# Aux_Connectors.net
KiCad netlist of a schematic drawn in Altium Designer
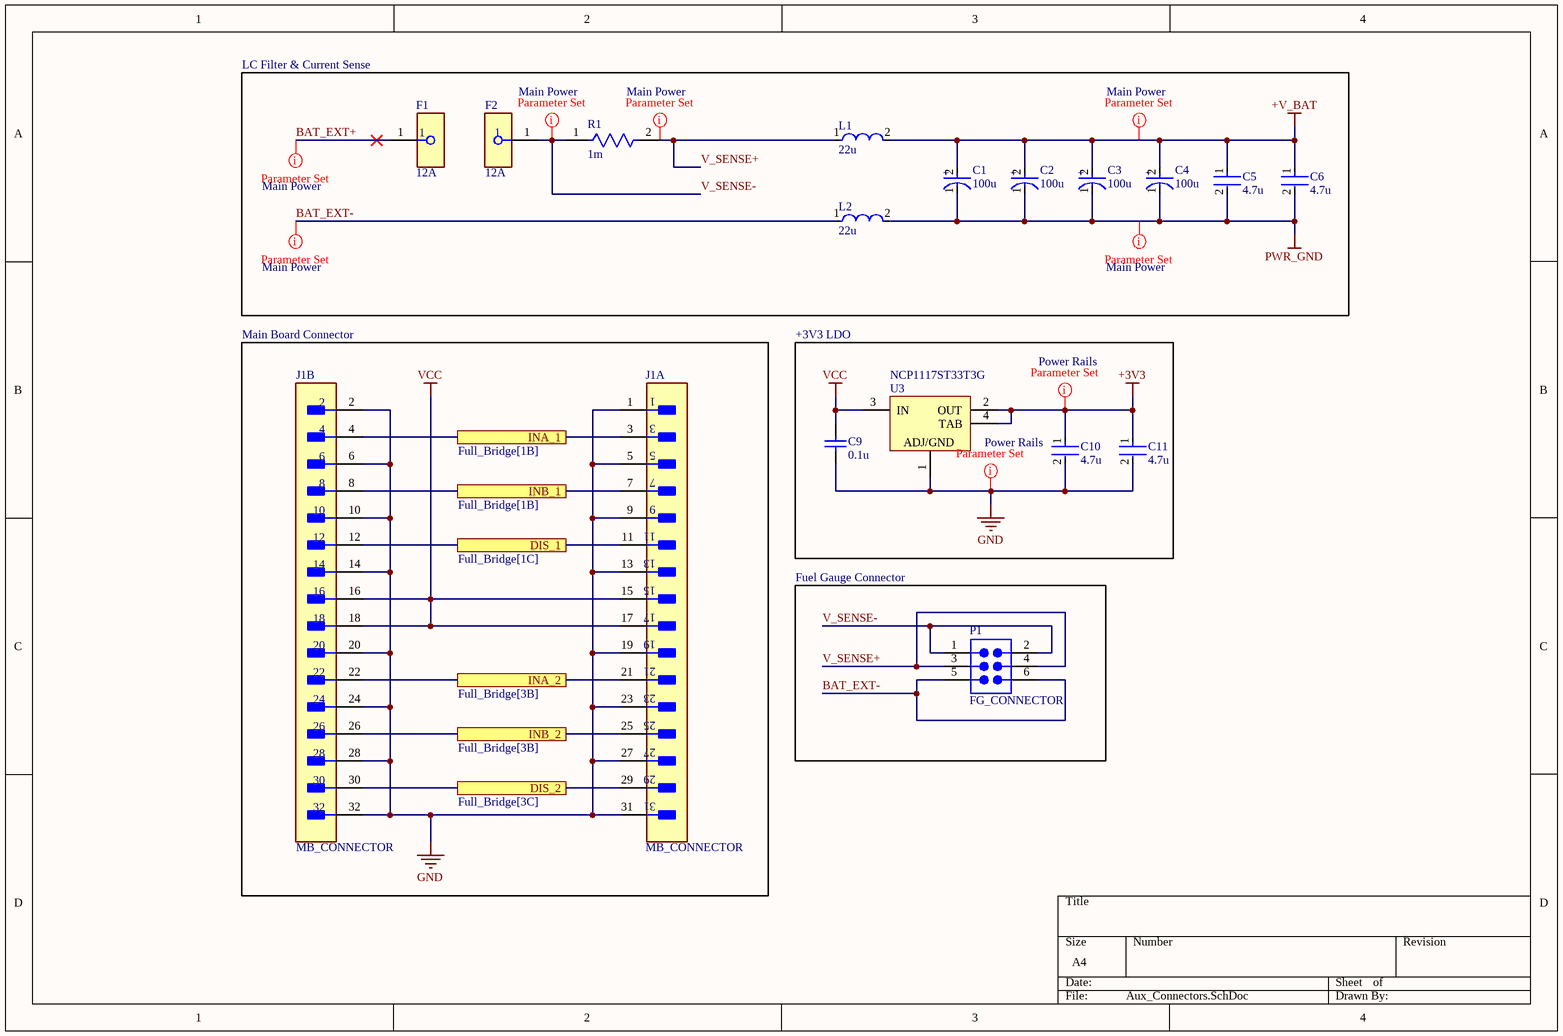
[diagram p0: Aux_Connectors.SchDoc]

(export (version "E")
  (design (tool "Eeschema 10.0.6"))
  (components
    (comp (ref "C1")
      (value "100u")
      (footprint "FP-EEHA-G-MFG")
      (description "Conductive Polymer Hybrid Aluminum Electrolytic Capacitors 100uF ±20% 50V RADIAL TH 10x9.5mm")
      (libsource (lib "Altium Content Vault") (part "a00bbbee19879c290e62620ae7e47b1"))
    )
    (comp (ref "C2")
      (value "100u")
      (footprint "FP-EEHA-G-MFG")
      (description "Conductive Polymer Hybrid Aluminum Electrolytic Capacitors 100uF ±20% 50V RADIAL TH 10x9.5mm")
      (libsource (lib "Altium Content Vault") (part "a00bbbee19879c290e62620ae7e47b1"))
    )
    (comp (ref "C3")
      (value "100u")
      (footprint "FP-EEHA-G-MFG")
      (description "Conductive Polymer Hybrid Aluminum Electrolytic Capacitors 100uF ±20% 50V RADIAL TH 10x9.5mm")
      (libsource (lib "Altium Content Vault") (part "a00bbbee19879c290e62620ae7e47b1"))
    )
    (comp (ref "C4")
      (value "100u")
      (footprint "FP-EEHA-G-MFG")
      (description "Conductive Polymer Hybrid Aluminum Electrolytic Capacitors 100uF ±20% 50V RADIAL TH 10x9.5mm")
      (libsource (lib "Altium Content Vault") (part "a00bbbee19879c290e62620ae7e47b1"))
    )
    (comp (ref "C5")
      (value "4.7u")
      (footprint "FP-GRM31C-0_2-e0_3_0_8-IPC_C")
      (description "Chip Multilayer Ceramic Capacitors for General Purpose, 1206, 4.7uF, X7R, 15%, 20%, 50V")
      (fields (field (name "TOLERANCE") "20%"))
      (libsource (lib "Altium Content Vault") (part "02cd4be3c70576c341d710602a673aa"))
    )
    (comp (ref "C6")
      (value "4.7u")
      (footprint "FP-GRM31C-0_2-e0_3_0_8-IPC_C")
      (description "Chip Multilayer Ceramic Capacitors for General Purpose, 1206, 4.7uF, X7R, 15%, 20%, 50V")
      (fields (field (name "TOLERANCE") "20%"))
      (libsource (lib "Altium Content Vault") (part "02cd4be3c70576c341d710602a673aa"))
    )
    (comp (ref "C9")
      (value "0.1u")
      (footprint "CAPC2013X145X48NL20T23")
      (fields (field (name "PART NUMBER") "VJ0805Y104KXAMR") (field (name "MANUFACTURER") "Vitramon"))
      (libsource (lib "Altium Content Vault") (part "CAP"))
    )
    (comp (ref "C10")
      (value "4.7u")
      (footprint "FP-GRM31C-0_2-e0_3_0_8-IPC_C")
      (description "Chip Multilayer Ceramic Capacitors for General Purpose, 1206, 4.7uF, X7R, 15%, 20%, 50V")
      (fields (field (name "TOLERANCE") "20%"))
      (libsource (lib "Altium Content Vault") (part "02cd4be3c70576c341d710602a673aa"))
    )
    (comp (ref "C11")
      (value "4.7u")
      (footprint "FP-GRM31C-0_2-e0_3_0_8-IPC_C")
      (description "Chip Multilayer Ceramic Capacitors for General Purpose, 1206, 4.7uF, X7R, 15%, 20%, 50V")
      (fields (field (name "TOLERANCE") "20%"))
      (libsource (lib "Altium Content Vault") (part "02cd4be3c70576c341d710602a673aa"))
    )
    (comp (ref "F1")
      (value "12A")
      (footprint "FP-8040_0001-MFG")
      (description "FUSE CLIP CARTRIDGE 600V 32A PCB")
      (fields (field (name "VOLTAGE") "600V"))
      (libsource (lib "") (part "98815daf2f2c152b0c43f5ab9800df6_1"))
    )
    (comp (ref "F2")
      (value "12A")
      (footprint "FP-8040_0001-MFG")
      (description "FUSE CLIP CARTRIDGE 600V 32A PCB")
      (fields (field (name "VOLTAGE") "600V"))
      (libsource (lib "Altium Content Vault") (part "98815daf2f2c152b0c43f5ab9800df6"))
    )
    (comp (ref "J1")
      (value "MB_CONNECTOR")
      (footprint "FP-MTSW-116-22-G-D-315-MFG")
      (description "CONN HEADER VERT 32POS 2.54MM")
      (libsource (lib "Altium Content Vault") (part "6c4afe00f0dd8865a914acb26556463"))
    )
    (comp (ref "L1")
      (value "22u")
      (footprint "FP-PA2247_223NLT-MFG")
      (description "FIXED IND 22UH 16A 15.8MOHM SMD")
      (libsource (lib "Altium Content Vault") (part "725321dda6339637d4d059423bc1c3c"))
    )
    (comp (ref "L2")
      (value "22u")
      (footprint "FP-PA2247_223NLT-MFG")
      (description "FIXED IND 22UH 16A 15.8MOHM SMD")
      (libsource (lib "Altium Content Vault") (part "725321dda6339637d4d059423bc1c3c"))
    )
    (comp (ref "P1")
      (value "FG_CONNECTOR")
      (footprint "SMTC-MTSW-103-07-X-D-244")
      (fields (field (name "MANUFACTURER") "Samtec") (field (name "PARTNUMBER") "MTSW-103-07-G-D-244"))
      (libsource (lib "Altium Content Vault") (part "SMTC-MTSW-103-07-X-D-244"))
    )
    (comp (ref "R1")
      (value "1m")
      (footprint "FP-WSLF2512-0_43-MFG")
      (description "RES 0.001 OHM 1% 5W 2512")
      (fields (field (name "TOLERANCE") "1%"))
      (libsource (lib "Altium Content Vault") (part "1029c3af85768c4190bb7ad29bc67b5"))
    )
    (comp (ref "U3")
      (value "NCP1117ST33T3G")
      (footprint "ONSC-SOT-223-4-318H-01_A_V")
      (fields (field (name "TOLERANCE") "1%"))
      (libsource (lib "Altium Content Vault") (part "ONSC-NCP1117-SOT223-4"))
    )
  )
  (nets
    (net (code "1") (name "+3V3") (class "Default")
      (node (ref "C10") (pin "1") (pinfunction "1_1") (pintype "passive"))
      (node (ref "C11") (pin "1") (pinfunction "1_1") (pintype "passive"))
      (node (ref "U3") (pin "2") (pinfunction "OUT_2") (pintype "power_in"))
      (node (ref "U3") (pin "4") (pinfunction "TAB_4") (pintype "passive"))
    )
    (net (code "2") (name "+V_BAT") (class "Default")
      (node (ref "C1") (pin "2") (pinfunction "A_2") (pintype "passive"))
      (node (ref "C2") (pin "2") (pinfunction "A_2") (pintype "passive"))
      (node (ref "C3") (pin "2") (pinfunction "A_2") (pintype "passive"))
      (node (ref "C4") (pin "2") (pinfunction "A_2") (pintype "passive"))
      (node (ref "C5") (pin "1") (pinfunction "1_1") (pintype "passive"))
      (node (ref "C6") (pin "1") (pinfunction "1_1") (pintype "passive"))
      (node (ref "L1") (pin "2") (pinfunction "2_2") (pintype "passive"))
    )
    (net (code "3") (name "/BAT_EXT+") (class "Default")
      (node (ref "F1") (pin "1") (pinfunction "1_1") (pintype "passive"))
    )
    (net (code "4") (name "/BAT_EXT-") (class "Default")
      (node (ref "L2") (pin "1") (pinfunction "1_1") (pintype "passive"))
      (node (ref "P1") (pin "5") (pinfunction "5_5") (pintype "passive"))
      (node (ref "P1") (pin "6") (pinfunction "6_6") (pintype "passive"))
    )
    (net (code "5") (name "/DIS_1") (class "Default")
      (node (ref "J1") (pin "11") (pinfunction "11_11") (pintype "passive"))
      (node (ref "J1") (pin "12") (pinfunction "12_12") (pintype "passive"))
    )
    (net (code "6") (name "/DIS_2") (class "Default")
      (node (ref "J1") (pin "29") (pinfunction "29_29") (pintype "passive"))
      (node (ref "J1") (pin "30") (pinfunction "30_30") (pintype "passive"))
    )
    (net (code "7") (name "/INA_1") (class "Default")
      (node (ref "J1") (pin "3") (pinfunction "3_3") (pintype "passive"))
      (node (ref "J1") (pin "4") (pinfunction "4_4") (pintype "passive"))
    )
    (net (code "8") (name "/INA_2") (class "Default")
      (node (ref "J1") (pin "21") (pinfunction "21_21") (pintype "passive"))
      (node (ref "J1") (pin "22") (pinfunction "22_22") (pintype "passive"))
    )
    (net (code "9") (name "/INB_1") (class "Default")
      (node (ref "J1") (pin "7") (pinfunction "7_7") (pintype "passive"))
      (node (ref "J1") (pin "8") (pinfunction "8_8") (pintype "passive"))
    )
    (net (code "10") (name "/INB_2") (class "Default")
      (node (ref "J1") (pin "25") (pinfunction "25_25") (pintype "passive"))
      (node (ref "J1") (pin "26") (pinfunction "26_26") (pintype "passive"))
    )
    (net (code "11") (name "/V_SENSE+") (class "Default")
      (node (ref "L1") (pin "1") (pinfunction "1_1") (pintype "passive"))
      (node (ref "P1") (pin "3") (pinfunction "3_3") (pintype "passive"))
      (node (ref "P1") (pin "4") (pinfunction "4_4") (pintype "passive"))
      (node (ref "R1") (pin "2") (pinfunction "2_2") (pintype "passive"))
    )
    (net (code "12") (name "/V_SENSE-") (class "Default")
      (node (ref "F2") (pin "1") (pinfunction "1_1") (pintype "passive"))
      (node (ref "P1") (pin "1") (pinfunction "1_1") (pintype "passive"))
      (node (ref "P1") (pin "2") (pinfunction "2_2") (pintype "passive"))
      (node (ref "R1") (pin "1") (pinfunction "1_1") (pintype "passive"))
    )
    (net (code "13") (name "GND") (class "Default")
      (node (ref "C10") (pin "2") (pinfunction "2_2") (pintype "passive"))
      (node (ref "C11") (pin "2") (pinfunction "2_2") (pintype "passive"))
      (node (ref "C9") (pin "1") (pinfunction "1_1") (pintype "passive"))
      (node (ref "J1") (pin "1") (pinfunction "1_1") (pintype "passive"))
      (node (ref "J1") (pin "10") (pinfunction "10_10") (pintype "passive"))
      (node (ref "J1") (pin "13") (pinfunction "13_13") (pintype "passive"))
      (node (ref "J1") (pin "14") (pinfunction "14_14") (pintype "passive"))
      (node (ref "J1") (pin "19") (pinfunction "19_19") (pintype "passive"))
      (node (ref "J1") (pin "2") (pinfunction "2_2") (pintype "passive"))
      (node (ref "J1") (pin "20") (pinfunction "20_20") (pintype "passive"))
      (node (ref "J1") (pin "23") (pinfunction "23_23") (pintype "passive"))
      (node (ref "J1") (pin "24") (pinfunction "24_24") (pintype "passive"))
      (node (ref "J1") (pin "27") (pinfunction "27_27") (pintype "passive"))
      (node (ref "J1") (pin "28") (pinfunction "28_28") (pintype "passive"))
      (node (ref "J1") (pin "31") (pinfunction "31_31") (pintype "passive"))
      (node (ref "J1") (pin "32") (pinfunction "32_32") (pintype "passive"))
      (node (ref "J1") (pin "5") (pinfunction "5_5") (pintype "passive"))
      (node (ref "J1") (pin "6") (pinfunction "6_6") (pintype "passive"))
      (node (ref "J1") (pin "9") (pinfunction "9_9") (pintype "passive"))
      (node (ref "U3") (pin "1") (pinfunction "ADJ/GND_1") (pintype "passive"))
    )
    (net (code "14") (name "PWR_GND") (class "Default")
      (node (ref "C1") (pin "1") (pinfunction "C_1") (pintype "passive"))
      (node (ref "C2") (pin "1") (pinfunction "C_1") (pintype "passive"))
      (node (ref "C3") (pin "1") (pinfunction "C_1") (pintype "passive"))
      (node (ref "C4") (pin "1") (pinfunction "C_1") (pintype "passive"))
      (node (ref "C5") (pin "2") (pinfunction "2_2") (pintype "passive"))
      (node (ref "C6") (pin "2") (pinfunction "2_2") (pintype "passive"))
      (node (ref "L2") (pin "2") (pinfunction "2_2") (pintype "passive"))
    )
    (net (code "15") (name "VCC") (class "Default")
      (node (ref "C9") (pin "2") (pinfunction "2_2") (pintype "passive"))
      (node (ref "J1") (pin "15") (pinfunction "15_15") (pintype "passive"))
      (node (ref "J1") (pin "16") (pinfunction "16_16") (pintype "passive"))
      (node (ref "J1") (pin "17") (pinfunction "17_17") (pintype "passive"))
      (node (ref "J1") (pin "18") (pinfunction "18_18") (pintype "passive"))
      (node (ref "U3") (pin "3") (pinfunction "IN_3") (pintype "power_in"))
    )
  )
)
